# untitled.net
KiCad netlist of a schematic drawn in EAGLE
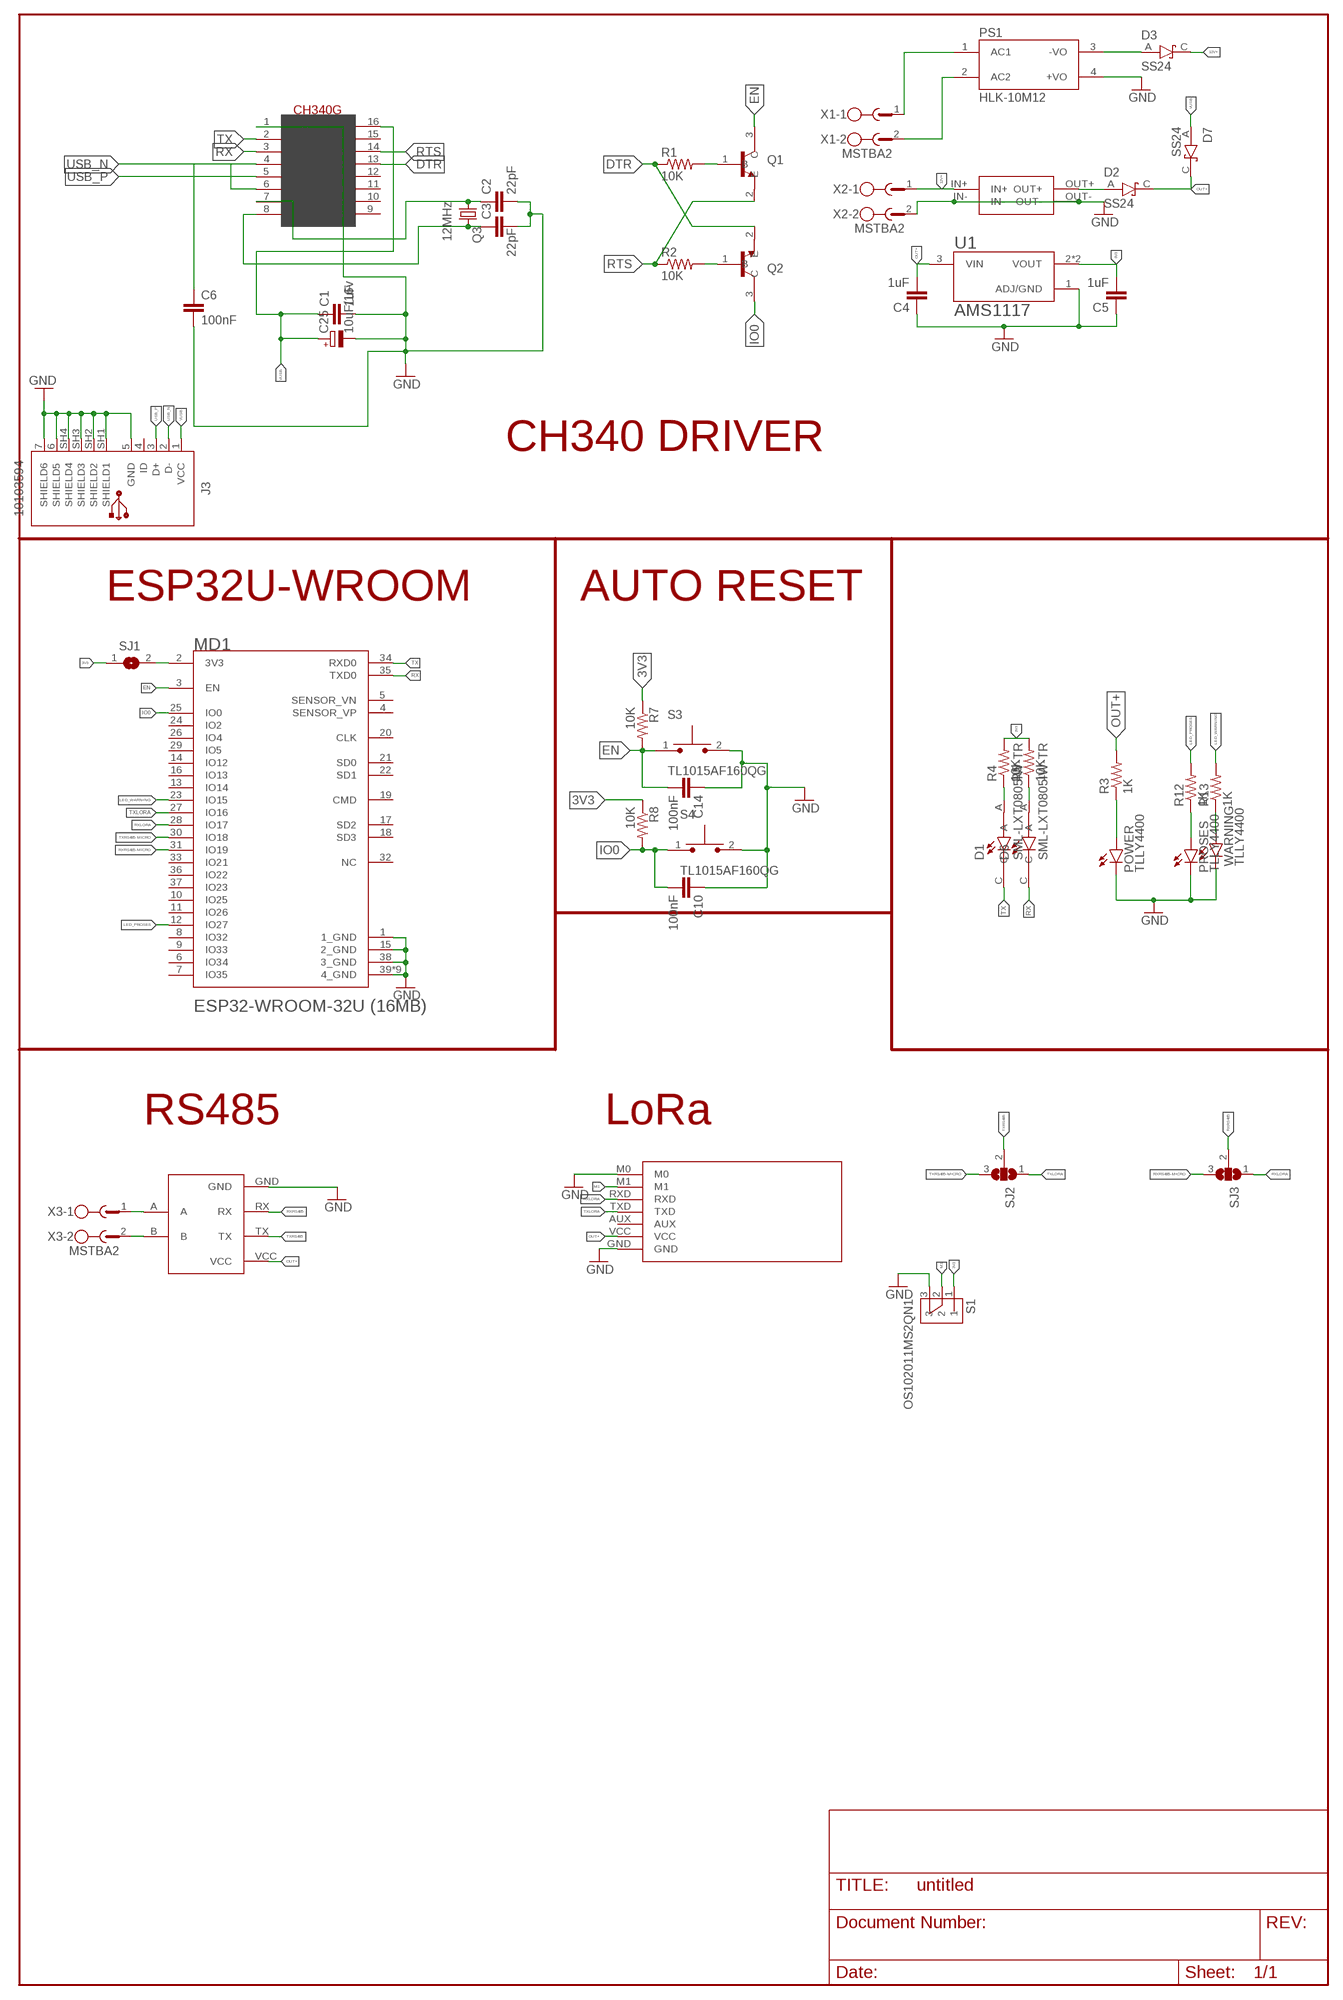
[diagram p0: schematic, sheet 1]

(export (version "E")
  (design (tool "Eeschema 10.0.6"))
  (components
    (comp (ref "C1")
      (value "1uF")
      (footprint "eagle-import:C0805K")
      (libsource (lib "eagle-import") (part "C-EUC0805K"))
    )
    (comp (ref "C2")
      (value "22pF")
      (footprint "eagle-import:C0805K")
      (libsource (lib "eagle-import") (part "C-EUC0805K"))
    )
    (comp (ref "C3")
      (value "22pF")
      (footprint "eagle-import:C0805K")
      (libsource (lib "eagle-import") (part "C-EUC0805K"))
    )
    (comp (ref "C4")
      (value "1uF")
      (footprint "eagle-import:C0805K")
      (libsource (lib "eagle-import") (part "C-EUC0805K"))
    )
    (comp (ref "C5")
      (value "1uF")
      (footprint "eagle-import:C0805K")
      (libsource (lib "eagle-import") (part "C-EUC0805K"))
    )
    (comp (ref "C6")
      (value "100nF")
      (footprint "eagle-import:C0805K")
      (libsource (lib "eagle-import") (part "C-EUC0805K"))
    )
    (comp (ref "C10")
      (value "100nF")
      (footprint "eagle-import:C0805K")
      (libsource (lib "eagle-import") (part "C-EUC0805K"))
    )
    (comp (ref "C14")
      (value "100nF")
      (footprint "eagle-import:C0805K")
      (libsource (lib "eagle-import") (part "C-EUC0805K"))
    )
    (comp (ref "C25")
      (value "10uF/16v")
      (footprint "eagle-import:153CLV-0505")
      (libsource (lib "eagle-import") (part "CPOL-EU153CLV-0505"))
    )
    (comp (ref "D1")
      (value "SML-LXT0805IW-TR")
      (footprint "eagle-import:LEDC2012X120N")
      (fields (field (name "MF") "Lumex Opto/Components"))
      (libsource (lib "eagle-import") (part "SML-LXT0805IW-TR"))
    )
    (comp (ref "D2")
      (value "SS24")
      (footprint "eagle-import:DIOM5336X265N")
      (fields (field (name "MF") "ON Semiconductor"))
      (libsource (lib "eagle-import") (part "SS24"))
    )
    (comp (ref "D3")
      (value "SS24")
      (footprint "eagle-import:DIOM5336X265N")
      (fields (field (name "MF") "ON Semiconductor"))
      (libsource (lib "eagle-import") (part "SS24"))
    )
    (comp (ref "D6")
      (value "SML-LXT0805IW-TR")
      (footprint "eagle-import:LEDC2012X120N")
      (fields (field (name "MF") "Lumex Opto/Components"))
      (libsource (lib "eagle-import") (part "SML-LXT0805IW-TR"))
    )
    (comp (ref "D7")
      (value "SS24")
      (footprint "eagle-import:DIOM5336X265N")
      (fields (field (name "MF") "ON Semiconductor"))
      (libsource (lib "eagle-import") (part "SS24"))
    )
    (comp (ref "EBYTEE220-900T22D1")
      (value "EBYTEE220-900T22D")
      (footprint "eagle-import:EBYTEE220-900T22D")
      (libsource (lib "eagle-import") (part "EBYTEE220-900T22D"))
    )
    (comp (ref "J3")
      (value "10103594")
      (footprint "eagle-import:10103594")
      (fields (field (name "MANUFACTURER") "Amphenol ICC (FCI)") (field (name "MPN") "10103594-0001LF"))
      (libsource (lib "eagle-import") (part "10103594"))
    )
    (comp (ref "MD1")
      (value "ESPRESSIF_SYSTEMS_ESP32-WROOM-32U_16MBESPRESSIF_SYSTEMS_ESP32-WROOM-32U_16MB_0_0")
      (footprint "eagle-import:ESPRESSIF_SYSTEMS_ESP32-WROOM-32U_16MB_0")
      (fields
        (field (name "DIGIKEY_PART_NUMBER") "1904-1028-1-ND")
        (field (name "MF") "Espressif Systems")
        (field (name "MOUSER_PART_NUMBER") "356-ES32WROOM32U16MB")
      )
      (libsource (lib "eagle-import") (part "ESPRESSIF_SYSTEMS_ESP32-WROOM-32U_16MBESPRESSIF_SYSTEMS_ESP32-WROOM-32U_16MB_0_0"))
    )
    (comp (ref "MINI1")
      (value "MINI560")
      (footprint "eagle-import:MINI560")
      (libsource (lib "eagle-import") (part "MINI560"))
    )
    (comp (ref "POWER")
      (value "TLLY4400")
      (footprint "eagle-import:LED3MM")
      (fields (field (name "MF") "VISHAY SEMICONDUCTOR"))
      (libsource (lib "eagle-import") (part "TLLY4400"))
    )
    (comp (ref "PROSES")
      (value "TLLY4400")
      (footprint "eagle-import:LED3MM")
      (fields (field (name "MF") "VISHAY SEMICONDUCTOR"))
      (libsource (lib "eagle-import") (part "TLLY4400"))
    )
    (comp (ref "PS1")
      (value "HLK-10M12")
      (footprint "eagle-import:CONV_HLK-10M12")
      (fields (field (name "MF") "Hi-link"))
      (libsource (lib "eagle-import") (part "HLK-10M12"))
    )
    (comp (ref "Q1")
      (value "MMBT3904")
      (footprint "eagle-import:SOT95P240X120-3N")
      (fields (field (name "MF") "STMicroelectronics"))
      (libsource (lib "eagle-import") (part "MMBT3904"))
    )
    (comp (ref "Q2")
      (value "MMBT3904")
      (footprint "eagle-import:SOT95P240X120-3N")
      (fields (field (name "MF") "STMicroelectronics"))
      (libsource (lib "eagle-import") (part "MMBT3904"))
    )
    (comp (ref "Q3")
      (value "12MHz")
      (footprint "eagle-import:SM49")
      (libsource (lib "eagle-import") (part "CRYSTALSM49"))
    )
    (comp (ref "R1")
      (value "10K")
      (footprint "eagle-import:M0805")
      (libsource (lib "eagle-import") (part "R-US_M0805"))
    )
    (comp (ref "R2")
      (value "10K")
      (footprint "eagle-import:M0805")
      (libsource (lib "eagle-import") (part "R-US_M0805"))
    )
    (comp (ref "R3")
      (value "1K")
      (footprint "eagle-import:M0805")
      (libsource (lib "eagle-import") (part "R-US_M0805"))
    )
    (comp (ref "R4")
      (value "10K")
      (footprint "eagle-import:M0805")
      (libsource (lib "eagle-import") (part "R-US_M0805"))
    )
    (comp (ref "R5")
      (value "10K")
      (footprint "eagle-import:M0805")
      (libsource (lib "eagle-import") (part "R-US_M0805"))
    )
    (comp (ref "R7")
      (value "10K")
      (footprint "eagle-import:M0805")
      (libsource (lib "eagle-import") (part "R-US_M0805"))
    )
    (comp (ref "R8")
      (value "10K")
      (footprint "eagle-import:M0805")
      (libsource (lib "eagle-import") (part "R-US_M0805"))
    )
    (comp (ref "R12")
      (value "1K")
      (footprint "eagle-import:M0805")
      (libsource (lib "eagle-import") (part "R-US_M0805"))
    )
    (comp (ref "R13")
      (value "1K")
      (footprint "eagle-import:M0805")
      (libsource (lib "eagle-import") (part "R-US_M0805"))
    )
    (comp (ref "S1")
      (value "OS102011MS2QN1")
      (footprint "eagle-import:SW_OS102011MS2QN1")
      (fields (field (name "MF") "C&K"))
      (libsource (lib "eagle-import") (part "OS102011MS2QN1"))
    )
    (comp (ref "S3")
      (value "TL1015AF160QG")
      (footprint "eagle-import:SW_TL1015AF160QG")
      (fields (field (name "MF") "E-Switch"))
      (libsource (lib "eagle-import") (part "TL1015AF160QG"))
    )
    (comp (ref "S4")
      (value "TL1015AF160QG")
      (footprint "eagle-import:SW_TL1015AF160QG")
      (fields (field (name "MF") "E-Switch"))
      (libsource (lib "eagle-import") (part "TL1015AF160QG"))
    )
    (comp (ref "SJ1") (value "SJ") (footprint "eagle-import:SJ") (libsource (lib "eagle-import") (part "SJ")))
    (comp (ref "SJ2")
      (value "SJ2W")
      (footprint "eagle-import:SJ_2")
      (libsource (lib "eagle-import") (part "SJ2W"))
    )
    (comp (ref "SJ3")
      (value "SJ2W")
      (footprint "eagle-import:SJ_2")
      (libsource (lib "eagle-import") (part "SJ2W"))
    )
    (comp (ref "TTL-RS1")
      (value "TTL-RS485")
      (footprint "eagle-import:TTL-RS485")
      (libsource (lib "eagle-import") (part "TTL-RS485"))
    )
    (comp (ref "U$2")
      (value "CH340G")
      (footprint "eagle-import:SOIC16")
      (libsource (lib "eagle-import") (part "CH340G"))
    )
    (comp (ref "U1")
      (value "AMS1117")
      (footprint "eagle-import:SOT229P700X180-4N")
      (fields (field (name "MF") "Advanced Monolithic Systems"))
      (libsource (lib "eagle-import") (part "AMS1117"))
    )
    (comp (ref "WARNING")
      (value "TLLY4400")
      (footprint "eagle-import:LED3MM")
      (fields (field (name "MF") "VISHAY SEMICONDUCTOR"))
      (libsource (lib "eagle-import") (part "TLLY4400"))
    )
    (comp (ref "X1")
      (value "MSTBA2")
      (footprint "eagle-import:MSTBA2")
      (fields (field (name "MF") "FARNELL") (field (name "MPN") "1757242"))
      (libsource (lib "eagle-import") (part "MSTBA2"))
    )
    (comp (ref "X2")
      (value "MSTBA2")
      (footprint "eagle-import:MSTBA2")
      (fields (field (name "MF") "FARNELL") (field (name "MPN") "1757242"))
      (libsource (lib "eagle-import") (part "MSTBA2"))
    )
    (comp (ref "X3")
      (value "MSTBA2")
      (footprint "eagle-import:MSTBA2")
      (fields (field (name "MF") "FARNELL") (field (name "MPN") "1757242"))
      (libsource (lib "eagle-import") (part "MSTBA2"))
    )
  )
  (nets
    (net (code "1") (name "3V3") (class "Default")
      (node (ref "C5") (pin "2") (pinfunction "2_2") (pintype "passive"))
      (node (ref "R4") (pin "2") (pinfunction "2_2") (pintype "passive"))
      (node (ref "R5") (pin "2") (pinfunction "2_2") (pintype "passive"))
      (node (ref "R7") (pin "1") (pinfunction "1_1") (pintype "passive"))
      (node (ref "R8") (pin "1") (pinfunction "1_1") (pintype "passive"))
      (node (ref "S1") (pin "1") (pinfunction "1_1") (pintype "passive"))
      (node (ref "SJ1") (pin "1") (pinfunction "1_1") (pintype "passive"))
      (node (ref "U1") (pin "2") (pinfunction "VOUT_2") (pintype "output"))
      (node (ref "U1") (pin "4") (pinfunction "VOUT_4") (pintype "output"))
    )
    (net (code "2") (name "12V+") (class "Default")
      (node (ref "D3") (pin "C") (pinfunction "K_C") (pintype "passive"))
      (node (ref "MINI1") (pin "IN+") (pinfunction "IN+_IN+") (pintype "bidirectional"))
      (node (ref "X2") (pin "1") (pinfunction "1_1") (pintype "passive"))
    )
    (net (code "3") (name "DTR") (class "Default")
      (node (ref "Q2") (pin "2") (pinfunction "E_2") (pintype "passive"))
      (node (ref "R1") (pin "1") (pinfunction "1_1") (pintype "passive"))
      (node (ref "U$2") (pin "13") (pinfunction "DTR_13") (pintype "bidirectional"))
    )
    (net (code "4") (name "EN") (class "Default")
      (node (ref "C14") (pin "2") (pinfunction "2_2") (pintype "passive"))
      (node (ref "MD1") (pin "3") (pinfunction "EN_3") (pintype "input"))
      (node (ref "Q1") (pin "3") (pinfunction "C_3") (pintype "passive"))
      (node (ref "R7") (pin "2") (pinfunction "2_2") (pintype "passive"))
      (node (ref "S3") (pin "1") (pinfunction "1_1") (pintype "passive"))
    )
    (net (code "5") (name "GND") (class "Default")
      (node (ref "C1") (pin "2") (pinfunction "2_2") (pintype "passive"))
      (node (ref "C10") (pin "1") (pinfunction "1_1") (pintype "passive"))
      (node (ref "C14") (pin "1") (pinfunction "1_1") (pintype "passive"))
      (node (ref "C2") (pin "2") (pinfunction "2_2") (pintype "passive"))
      (node (ref "C25") (pin "-") (pinfunction "-_-") (pintype "passive"))
      (node (ref "C3") (pin "2") (pinfunction "2_2") (pintype "passive"))
      (node (ref "C4") (pin "1") (pinfunction "1_1") (pintype "passive"))
      (node (ref "C5") (pin "1") (pinfunction "1_1") (pintype "passive"))
      (node (ref "C6") (pin "2") (pinfunction "2_2") (pintype "passive"))
      (node (ref "EBYTEE220-900T22D1") (pin "GND") (pinfunction "GND_GND") (pintype "bidirectional"))
      (node (ref "EBYTEE220-900T22D1") (pin "M0") (pinfunction "M0_M0") (pintype "bidirectional"))
      (node (ref "J3") (pin "5") (pinfunction "GND_5") (pintype "power_in"))
      (node (ref "J3") (pin "6") (pinfunction "SHIELD5_6") (pintype "power_in"))
      (node (ref "J3") (pin "7") (pinfunction "SHIELD6_7") (pintype "power_in"))
      (node (ref "J3") (pin "SH1") (pinfunction "SHIELD1_SH1") (pintype "power_in"))
      (node (ref "J3") (pin "SH2") (pinfunction "SHIELD2_SH2") (pintype "power_in"))
      (node (ref "J3") (pin "SH3") (pinfunction "SHIELD3_SH3") (pintype "power_in"))
      (node (ref "J3") (pin "SH4") (pinfunction "SHIELD4_SH4") (pintype "power_in"))
      (node (ref "MD1") (pin "1") (pinfunction "1_GND_1") (pintype "power_in"))
      (node (ref "MD1") (pin "15") (pinfunction "2_GND_15") (pintype "power_in"))
      (node (ref "MD1") (pin "38") (pinfunction "3_GND_38") (pintype "power_in"))
      (node (ref "MD1") (pin "39") (pinfunction "4_GND_39") (pintype "power_in"))
      (node (ref "MD1") (pin "39-2") (pinfunction "4_GND_39-2") (pintype "power_in"))
      (node (ref "MD1") (pin "39-3") (pinfunction "4_GND_39-3") (pintype "power_in"))
      (node (ref "MD1") (pin "39-4") (pinfunction "4_GND_39-4") (pintype "power_in"))
      (node (ref "MD1") (pin "39-5") (pinfunction "4_GND_39-5") (pintype "power_in"))
      (node (ref "MD1") (pin "39-6") (pinfunction "4_GND_39-6") (pintype "power_in"))
      (node (ref "MD1") (pin "39-7") (pinfunction "4_GND_39-7") (pintype "power_in"))
      (node (ref "MD1") (pin "39-8") (pinfunction "4_GND_39-8") (pintype "power_in"))
      (node (ref "MD1") (pin "39-9") (pinfunction "4_GND_39-9") (pintype "power_in"))
      (node (ref "MINI1") (pin "IN-") (pinfunction "IN-_IN-") (pintype "bidirectional"))
      (node (ref "MINI1") (pin "OUT-") (pinfunction "OUT-_OUT-") (pintype "bidirectional"))
      (node (ref "POWER") (pin "K") (pinfunction "C_K") (pintype "passive"))
      (node (ref "PROSES") (pin "K") (pinfunction "C_K") (pintype "passive"))
      (node (ref "PS1") (pin "4") (pinfunction "+VO_4") (pintype "output"))
      (node (ref "S1") (pin "3") (pinfunction "3_3") (pintype "passive"))
      (node (ref "S3") (pin "2") (pinfunction "2_2") (pintype "passive"))
      (node (ref "S4") (pin "2") (pinfunction "2_2") (pintype "passive"))
      (node (ref "TTL-RS1") (pin "GND") (pinfunction "GND_GND") (pintype "bidirectional"))
      (node (ref "U$2") (pin "1") (pinfunction "GND_1") (pintype "bidirectional"))
      (node (ref "U1") (pin "1") (pinfunction "ADJ/GND_1") (pintype "power_in"))
      (node (ref "WARNING") (pin "K") (pinfunction "C_K") (pintype "passive"))
      (node (ref "X2") (pin "2") (pinfunction "1_2") (pintype "passive"))
    )
    (net (code "6") (name "IO0") (class "Default")
      (node (ref "C10") (pin "2") (pinfunction "2_2") (pintype "passive"))
      (node (ref "MD1") (pin "25") (pinfunction "IO0_25") (pintype "bidirectional"))
      (node (ref "Q2") (pin "3") (pinfunction "C_3") (pintype "passive"))
      (node (ref "R8") (pin "2") (pinfunction "2_2") (pintype "passive"))
      (node (ref "S4") (pin "1") (pinfunction "1_1") (pintype "passive"))
    )
    (net (code "7") (name "LED_PROSES") (class "Default")
      (node (ref "MD1") (pin "12") (pinfunction "IO27_12") (pintype "bidirectional"))
      (node (ref "R12") (pin "2") (pinfunction "2_2") (pintype "passive"))
    )
    (net (code "8") (name "LED_WARNING") (class "Default")
      (node (ref "MD1") (pin "23") (pinfunction "IO15_23") (pintype "bidirectional"))
      (node (ref "R13") (pin "2") (pinfunction "2_2") (pintype "passive"))
    )
    (net (code "9") (name "M1") (class "Default")
      (node (ref "EBYTEE220-900T22D1") (pin "M1") (pinfunction "M1_M1") (pintype "bidirectional"))
      (node (ref "S1") (pin "2") (pinfunction "2_2") (pintype "passive"))
    )
    (net (code "10") (name "Net-(D1-PadA)") (class "Default")
      (node (ref "D1") (pin "A") (pinfunction "A_A") (pintype "passive"))
      (node (ref "R4") (pin "1") (pinfunction "1_1") (pintype "passive"))
    )
    (net (code "11") (name "Net-(D2-PadA)") (class "Default")
      (node (ref "D2") (pin "A") (pinfunction "A_A") (pintype "passive"))
      (node (ref "MINI1") (pin "OUT+") (pinfunction "OUT+_OUT+") (pintype "bidirectional"))
    )
    (net (code "12") (name "Net-(D6-PadA)") (class "Default")
      (node (ref "D6") (pin "A") (pinfunction "A_A") (pintype "passive"))
      (node (ref "R5") (pin "1") (pinfunction "1_1") (pintype "passive"))
    )
    (net (code "13") (name "Net-(MD1-3V3)") (class "Default")
      (node (ref "MD1") (pin "2") (pinfunction "3V3_2") (pintype "power_in"))
      (node (ref "SJ1") (pin "2") (pinfunction "2_2") (pintype "passive"))
    )
    (net (code "14") (name "Net-(POWER-PadA)") (class "Default")
      (node (ref "POWER") (pin "A") (pinfunction "A_A") (pintype "passive"))
      (node (ref "R3") (pin "1") (pinfunction "1_1") (pintype "passive"))
    )
    (net (code "15") (name "Net-(PROSES-PadA)") (class "Default")
      (node (ref "PROSES") (pin "A") (pinfunction "A_A") (pintype "passive"))
      (node (ref "R12") (pin "1") (pinfunction "1_1") (pintype "passive"))
    )
    (net (code "16") (name "Net-(PS1--VO)") (class "Default")
      (node (ref "D3") (pin "A") (pinfunction "A_A") (pintype "passive"))
      (node (ref "PS1") (pin "3") (pinfunction "-VO_3") (pintype "output"))
    )
    (net (code "17") (name "Net-(PS1-AC1)") (class "Default")
      (node (ref "PS1") (pin "1") (pinfunction "AC1_1") (pintype "input"))
      (node (ref "X1") (pin "1") (pinfunction "1_1") (pintype "passive"))
    )
    (net (code "18") (name "Net-(PS1-AC2)") (class "Default")
      (node (ref "PS1") (pin "2") (pinfunction "AC2_2") (pintype "input"))
      (node (ref "X1") (pin "2") (pinfunction "1_2") (pintype "passive"))
    )
    (net (code "19") (name "Net-(Q1-B)") (class "Default")
      (node (ref "Q1") (pin "1") (pinfunction "B_1") (pintype "passive"))
      (node (ref "R1") (pin "2") (pinfunction "2_2") (pintype "passive"))
    )
    (net (code "20") (name "Net-(Q2-B)") (class "Default")
      (node (ref "Q2") (pin "1") (pinfunction "B_1") (pintype "passive"))
      (node (ref "R2") (pin "2") (pinfunction "2_2") (pintype "passive"))
    )
    (net (code "21") (name "Net-(R13-Pad1)") (class "Default")
      (node (ref "R13") (pin "1") (pinfunction "1_1") (pintype "passive"))
      (node (ref "WARNING") (pin "A") (pinfunction "A_A") (pintype "passive"))
    )
    (net (code "22") (name "Net-(TTL-RS1-PadA)") (class "Default")
      (node (ref "TTL-RS1") (pin "A") (pinfunction "A_A") (pintype "bidirectional"))
      (node (ref "X3") (pin "1") (pinfunction "1_1") (pintype "passive"))
    )
    (net (code "23") (name "Net-(U$2-V3)") (class "Default")
      (node (ref "C6") (pin "1") (pinfunction "1_1") (pintype "passive"))
      (node (ref "U$2") (pin "4") (pinfunction "V3_4") (pintype "bidirectional"))
    )
    (net (code "24") (name "Net-(U$2-XI)") (class "Default")
      (node (ref "C2") (pin "1") (pinfunction "1_1") (pintype "passive"))
      (node (ref "Q3") (pin "1") (pinfunction "1_1") (pintype "passive"))
      (node (ref "U$2") (pin "7") (pinfunction "XI_7") (pintype "bidirectional"))
    )
    (net (code "25") (name "Net-(U$2-XO)") (class "Default")
      (node (ref "C3") (pin "1") (pinfunction "1_1") (pintype "passive"))
      (node (ref "Q3") (pin "2") (pinfunction "2_2") (pintype "passive"))
      (node (ref "U$2") (pin "8") (pinfunction "XO_8") (pintype "bidirectional"))
    )
    (net (code "26") (name "Net-(X3B-1)") (class "Default")
      (node (ref "TTL-RS1") (pin "B") (pinfunction "B_B") (pintype "bidirectional"))
      (node (ref "X3") (pin "2") (pinfunction "1_2") (pintype "passive"))
    )
    (net (code "27") (name "OUT+") (class "Default")
      (node (ref "C4") (pin "2") (pinfunction "2_2") (pintype "passive"))
      (node (ref "D2") (pin "C") (pinfunction "K_C") (pintype "passive"))
      (node (ref "D7") (pin "C") (pinfunction "K_C") (pintype "passive"))
      (node (ref "EBYTEE220-900T22D1") (pin "VCC") (pinfunction "VCC_VCC") (pintype "bidirectional"))
      (node (ref "R3") (pin "2") (pinfunction "2_2") (pintype "passive"))
      (node (ref "TTL-RS1") (pin "VCC") (pinfunction "VCC_VCC") (pintype "bidirectional"))
      (node (ref "U1") (pin "3") (pinfunction "VIN_3") (pintype "input"))
    )
    (net (code "28") (name "RTS") (class "Default")
      (node (ref "Q1") (pin "2") (pinfunction "E_2") (pintype "passive"))
      (node (ref "R2") (pin "1") (pinfunction "1_1") (pintype "passive"))
      (node (ref "U$2") (pin "14") (pinfunction "RTS_14") (pintype "bidirectional"))
    )
    (net (code "29") (name "RX") (class "Default")
      (node (ref "D6") (pin "C") (pinfunction "C_C") (pintype "passive"))
      (node (ref "MD1") (pin "35") (pinfunction "TXD0_35") (pintype "bidirectional"))
      (node (ref "U$2") (pin "3") (pinfunction "RX_3") (pintype "bidirectional"))
    )
    (net (code "30") (name "RXLORA") (class "Default")
      (node (ref "EBYTEE220-900T22D1") (pin "RXD") (pinfunction "RXD_RXD") (pintype "bidirectional"))
      (node (ref "MD1") (pin "28") (pinfunction "IO17_28") (pintype "bidirectional"))
      (node (ref "SJ3") (pin "1") (pinfunction "1_1") (pintype "passive"))
    )
    (net (code "31") (name "RXRS485") (class "Default")
      (node (ref "SJ3") (pin "2") (pinfunction "2_2") (pintype "passive"))
      (node (ref "TTL-RS1") (pin "RX") (pinfunction "RX_RX") (pintype "bidirectional"))
    )
    (net (code "32") (name "RXRS485-MICRO") (class "Default")
      (node (ref "MD1") (pin "31") (pinfunction "IO19_31") (pintype "bidirectional"))
      (node (ref "SJ3") (pin "3") (pinfunction "3_3") (pintype "passive"))
    )
    (net (code "33") (name "TX") (class "Default")
      (node (ref "D1") (pin "C") (pinfunction "C_C") (pintype "passive"))
      (node (ref "MD1") (pin "34") (pinfunction "RXD0_34") (pintype "bidirectional"))
      (node (ref "U$2") (pin "2") (pinfunction "TX_2") (pintype "bidirectional"))
    )
    (net (code "34") (name "TXLORA") (class "Default")
      (node (ref "EBYTEE220-900T22D1") (pin "TXD") (pinfunction "TXD_TXD") (pintype "bidirectional"))
      (node (ref "MD1") (pin "27") (pinfunction "IO16_27") (pintype "bidirectional"))
      (node (ref "SJ2") (pin "1") (pinfunction "1_1") (pintype "passive"))
    )
    (net (code "35") (name "TXRS485") (class "Default")
      (node (ref "SJ2") (pin "2") (pinfunction "2_2") (pintype "passive"))
      (node (ref "TTL-RS1") (pin "TX") (pinfunction "TX_TX") (pintype "bidirectional"))
    )
    (net (code "36") (name "TXRS485-MICRO") (class "Default")
      (node (ref "MD1") (pin "30") (pinfunction "IO18_30") (pintype "bidirectional"))
      (node (ref "SJ2") (pin "3") (pinfunction "3_3") (pintype "passive"))
    )
    (net (code "37") (name "USB_N") (class "Default")
      (node (ref "J3") (pin "2") (pinfunction "D-_2") (pintype "bidirectional"))
      (node (ref "U$2") (pin "6") (pinfunction "D-_6") (pintype "bidirectional"))
    )
    (net (code "38") (name "USB_P") (class "Default")
      (node (ref "J3") (pin "3") (pinfunction "D+_3") (pintype "bidirectional"))
      (node (ref "U$2") (pin "5") (pinfunction "D+_5") (pintype "bidirectional"))
    )
    (net (code "39") (name "VUSB") (class "Default")
      (node (ref "C1") (pin "1") (pinfunction "1_1") (pintype "passive"))
      (node (ref "C25") (pin "+") (pinfunction "+_+") (pintype "passive"))
      (node (ref "D7") (pin "A") (pinfunction "A_A") (pintype "passive"))
      (node (ref "J3") (pin "1") (pinfunction "VCC_1") (pintype "power_in"))
      (node (ref "U$2") (pin "16") (pinfunction "VCC_16") (pintype "bidirectional"))
    )
    (net (code "40") (name "unconnected-(EBYTEE220-900T22D1-PadAUX)") (class "Default")
      (node (ref "EBYTEE220-900T22D1") (pin "AUX") (pinfunction "AUX_AUX") (pintype "bidirectional"))
    )
    (net (code "41") (name "unconnected-(J3-ID-Pad4)") (class "Default")
      (node (ref "J3") (pin "4") (pinfunction "ID_4") (pintype "bidirectional"))
    )
    (net (code "42") (name "unconnected-(MD1-CLK-Pad20)") (class "Default")
      (node (ref "MD1") (pin "20") (pinfunction "CLK_20") (pintype "bidirectional"))
    )
    (net (code "43") (name "unconnected-(MD1-CMD-Pad19)") (class "Default")
      (node (ref "MD1") (pin "19") (pinfunction "CMD_19") (pintype "bidirectional"))
    )
    (net (code "44") (name "unconnected-(MD1-IO2-Pad24)") (class "Default")
      (node (ref "MD1") (pin "24") (pinfunction "IO2_24") (pintype "bidirectional"))
    )
    (net (code "45") (name "unconnected-(MD1-IO4-Pad26)") (class "Default")
      (node (ref "MD1") (pin "26") (pinfunction "IO4_26") (pintype "bidirectional"))
    )
    (net (code "46") (name "unconnected-(MD1-IO5-Pad29)") (class "Default")
      (node (ref "MD1") (pin "29") (pinfunction "IO5_29") (pintype "bidirectional"))
    )
    (net (code "47") (name "unconnected-(MD1-IO12-Pad14)") (class "Default")
      (node (ref "MD1") (pin "14") (pinfunction "IO12_14") (pintype "bidirectional"))
    )
    (net (code "48") (name "unconnected-(MD1-IO13-Pad16)") (class "Default")
      (node (ref "MD1") (pin "16") (pinfunction "IO13_16") (pintype "bidirectional"))
    )
    (net (code "49") (name "unconnected-(MD1-IO14-Pad13)") (class "Default")
      (node (ref "MD1") (pin "13") (pinfunction "IO14_13") (pintype "bidirectional"))
    )
    (net (code "50") (name "unconnected-(MD1-IO21-Pad33)") (class "Default")
      (node (ref "MD1") (pin "33") (pinfunction "IO21_33") (pintype "bidirectional"))
    )
    (net (code "51") (name "unconnected-(MD1-IO22-Pad36)") (class "Default")
      (node (ref "MD1") (pin "36") (pinfunction "IO22_36") (pintype "bidirectional"))
    )
    (net (code "52") (name "unconnected-(MD1-IO23-Pad37)") (class "Default")
      (node (ref "MD1") (pin "37") (pinfunction "IO23_37") (pintype "bidirectional"))
    )
    (net (code "53") (name "unconnected-(MD1-IO25-Pad10)") (class "Default")
      (node (ref "MD1") (pin "10") (pinfunction "IO25_10") (pintype "bidirectional"))
    )
    (net (code "54") (name "unconnected-(MD1-IO26-Pad11)") (class "Default")
      (node (ref "MD1") (pin "11") (pinfunction "IO26_11") (pintype "bidirectional"))
    )
    (net (code "55") (name "unconnected-(MD1-IO32-Pad8)") (class "Default")
      (node (ref "MD1") (pin "8") (pinfunction "IO32_8") (pintype "bidirectional"))
    )
    (net (code "56") (name "unconnected-(MD1-IO33-Pad9)") (class "Default")
      (node (ref "MD1") (pin "9") (pinfunction "IO33_9") (pintype "bidirectional"))
    )
    (net (code "57") (name "unconnected-(MD1-IO34-Pad6)") (class "Default")
      (node (ref "MD1") (pin "6") (pinfunction "IO34_6") (pintype "bidirectional"))
    )
    (net (code "58") (name "unconnected-(MD1-IO35-Pad7)") (class "Default")
      (node (ref "MD1") (pin "7") (pinfunction "IO35_7") (pintype "bidirectional"))
    )
    (net (code "59") (name "unconnected-(MD1-NC-Pad32)") (class "Default")
      (node (ref "MD1") (pin "32") (pinfunction "NC_32") (pintype "passive"))
    )
    (net (code "60") (name "unconnected-(MD1-SD0-Pad21)") (class "Default")
      (node (ref "MD1") (pin "21") (pinfunction "SD0_21") (pintype "bidirectional"))
    )
    (net (code "61") (name "unconnected-(MD1-SD1-Pad22)") (class "Default")
      (node (ref "MD1") (pin "22") (pinfunction "SD1_22") (pintype "bidirectional"))
    )
    (net (code "62") (name "unconnected-(MD1-SD2-Pad17)") (class "Default")
      (node (ref "MD1") (pin "17") (pinfunction "SD2_17") (pintype "bidirectional"))
    )
    (net (code "63") (name "unconnected-(MD1-SD3-Pad18)") (class "Default")
      (node (ref "MD1") (pin "18") (pinfunction "SD3_18") (pintype "bidirectional"))
    )
    (net (code "64") (name "unconnected-(MD1-SENSOR_VN-Pad5)") (class "Default")
      (node (ref "MD1") (pin "5") (pinfunction "SENSOR_VN_5") (pintype "input"))
    )
    (net (code "65") (name "unconnected-(MD1-SENSOR_VP-Pad4)") (class "Default")
      (node (ref "MD1") (pin "4") (pinfunction "SENSOR_VP_4") (pintype "input"))
    )
    (net (code "66") (name "unconnected-(U$2-CTS-Pad9)") (class "Default")
      (node (ref "U$2") (pin "9") (pinfunction "CTS_9") (pintype "bidirectional"))
    )
    (net (code "67") (name "unconnected-(U$2-DCD-Pad12)") (class "Default")
      (node (ref "U$2") (pin "12") (pinfunction "DCD_12") (pintype "bidirectional"))
    )
    (net (code "68") (name "unconnected-(U$2-DSR-Pad10)") (class "Default")
      (node (ref "U$2") (pin "10") (pinfunction "DSR_10") (pintype "bidirectional"))
    )
    (net (code "69") (name "unconnected-(U$2-RI-Pad11)") (class "Default")
      (node (ref "U$2") (pin "11") (pinfunction "RI_11") (pintype "bidirectional"))
    )
    (net (code "70") (name "unconnected-(U$2-RS232-Pad15)") (class "Default")
      (node (ref "U$2") (pin "15") (pinfunction "RS232_15") (pintype "bidirectional"))
    )
  )
)
